# PS2toUSB.net
KiCad netlist of a schematic drawn in EasyEDA Pro
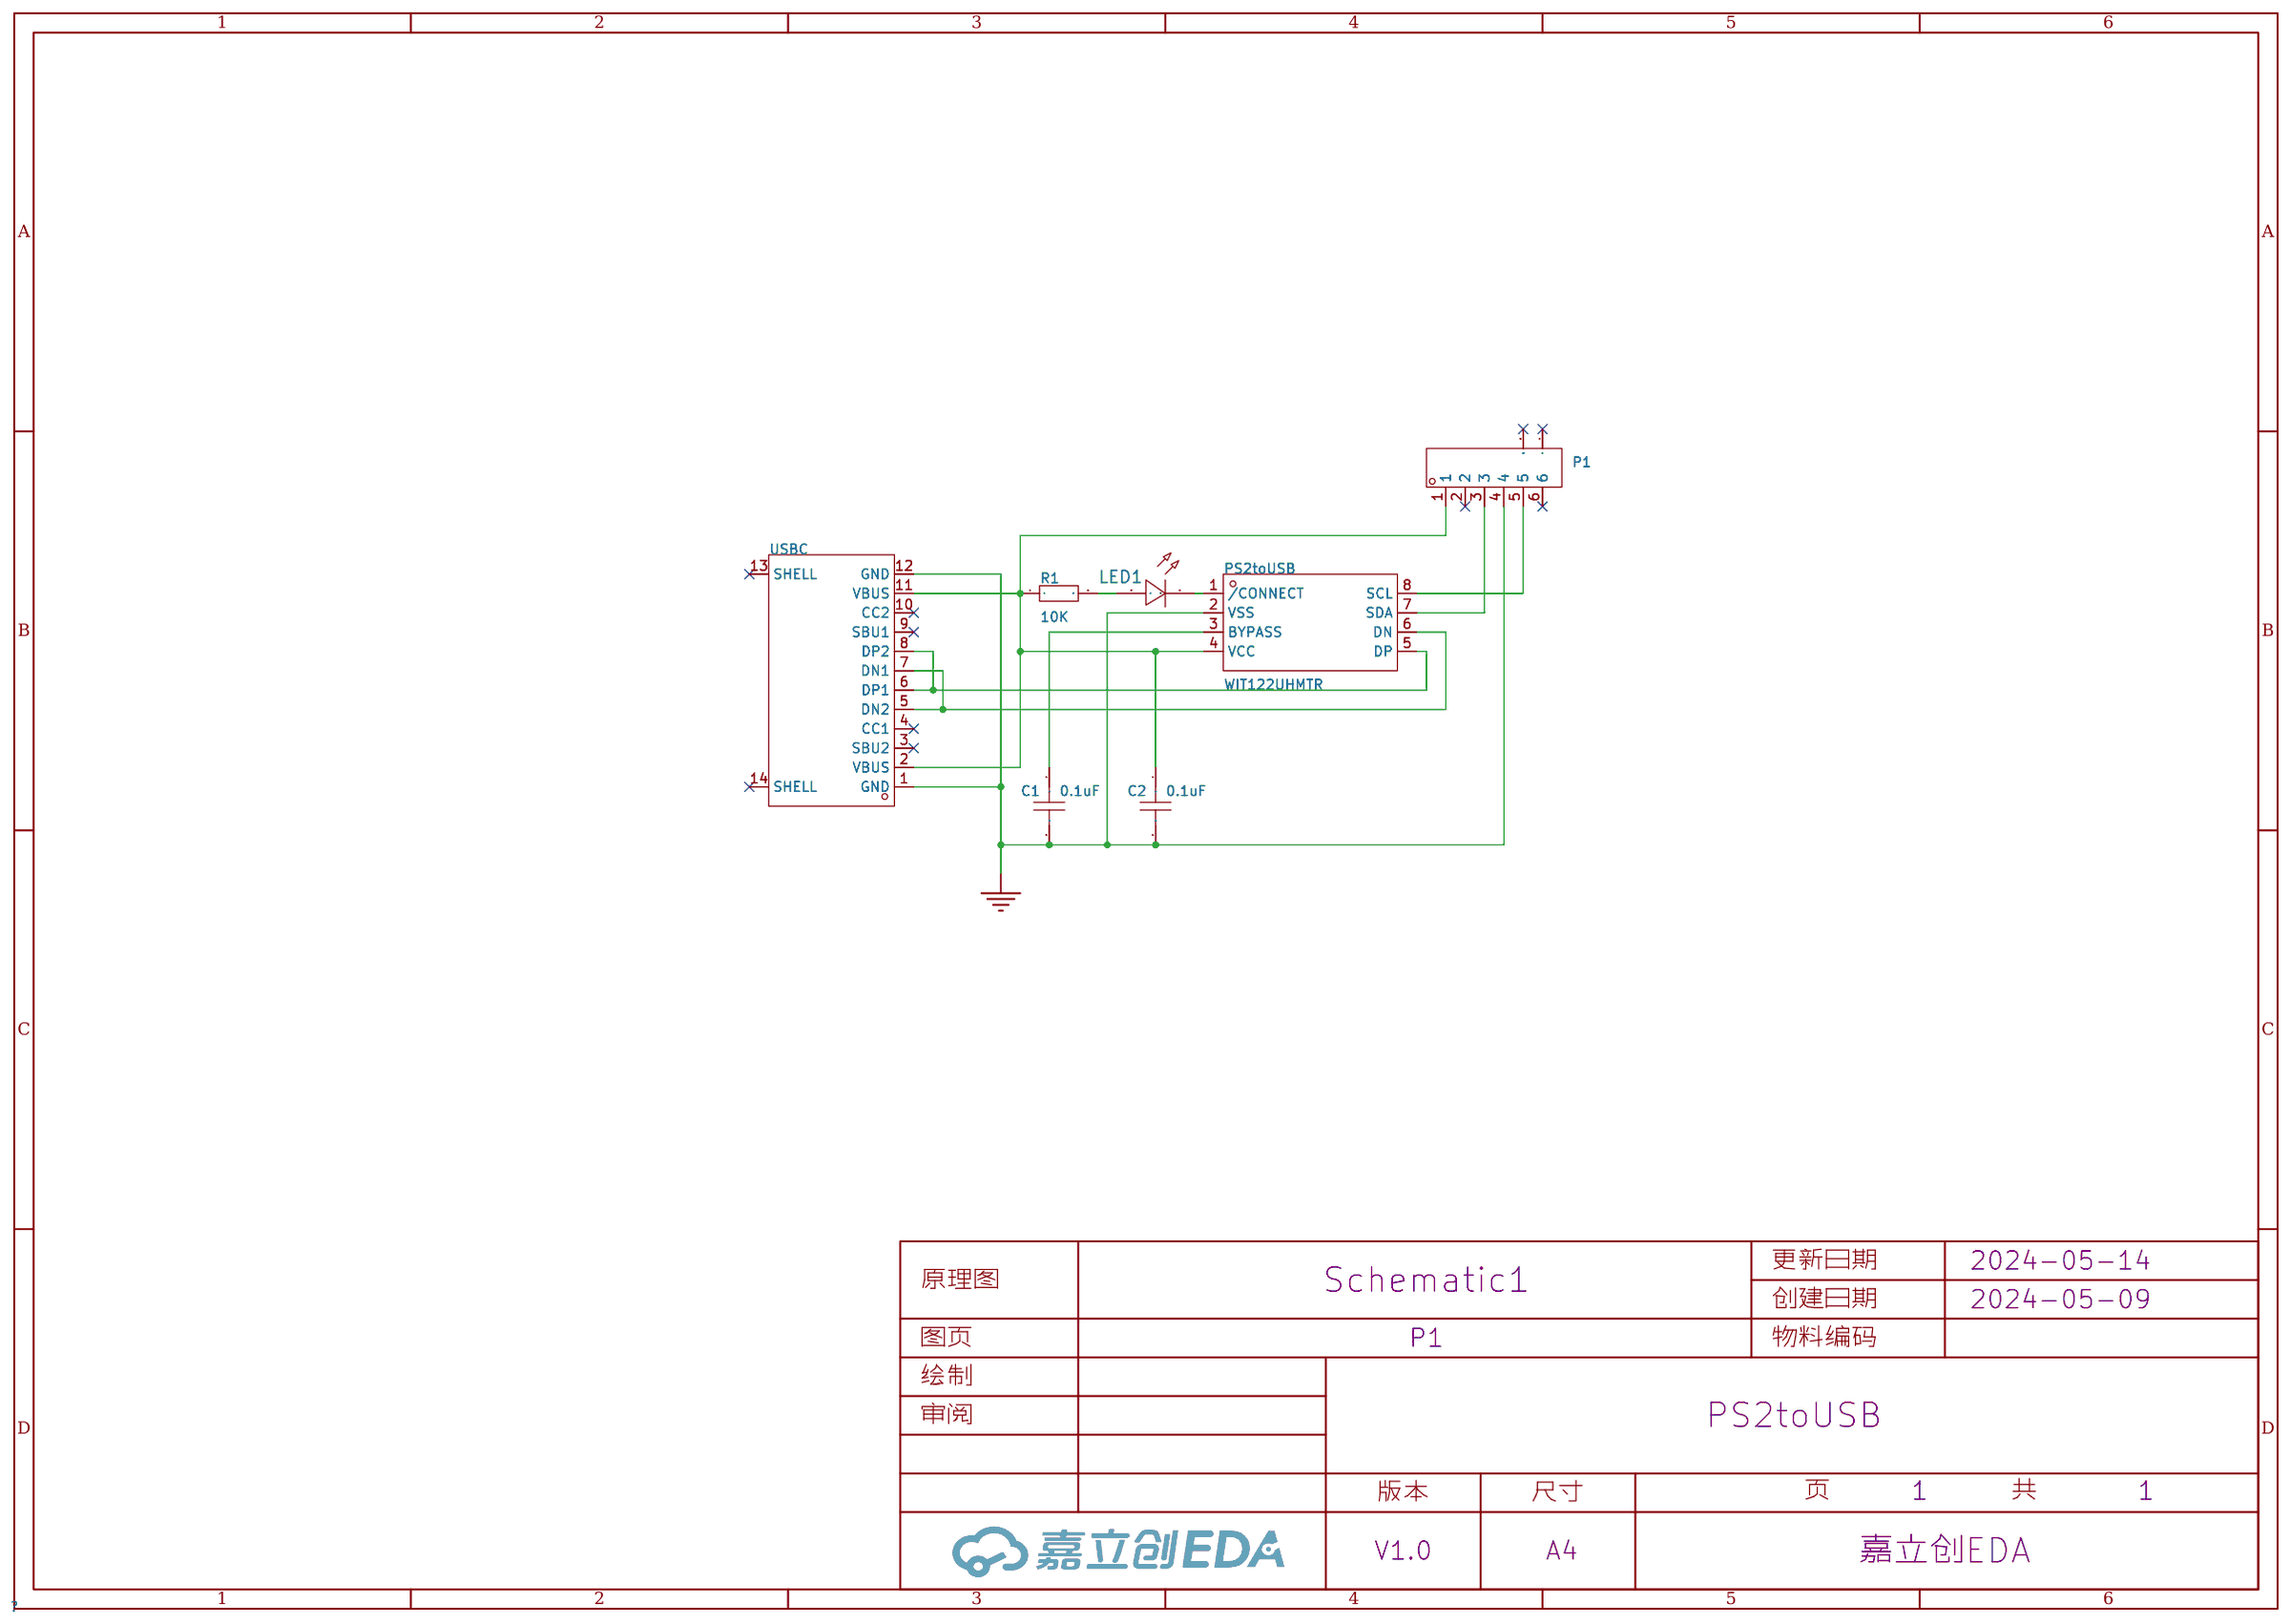
[diagram p0: schematic sheet]

(export (version "E")
  (design (tool "Eeschema 10.0.6"))
  (components
    (comp (ref "C1")
      (value "0.1uF")
      (footprint "easyedapro:C0603")
      (libsource (lib "easyedapro") (part "CapAcitance"))
    )
    (comp (ref "C2")
      (value "0.1uF")
      (footprint "easyedapro:C0603")
      (libsource (lib "easyedapro") (part "CapAcitance"))
    )
    (comp (ref "LED1")
      (value "~")
      (footprint "easyedapro:LED_0603")
      (libsource (lib "easyedapro") (part "LED_R"))
    )
    (comp (ref "P1")
      (value "VCC")
      (footprint "easyedapro:FPC-SMD_C47271")
      (description "锁定特性:抽屉式;触点类型:上接;触点数量:6P;间距:1mm;安装类型:卧贴;工作温度范围:-25°C~+85°C;")
      (fields (field (name "Manufacturer Part") "1.0-6P上接") (field (name "Manufacturer") "BOOMELE(博穆精密)"))
      (libsource (lib "easyedapro") (part "FPC 1.0mmpitch 6P Pull type Pick up"))
    )
    (comp (ref "PS2toUSB")
      (value "WIT122UHMTR")
      (footprint "easyedapro:SOIC-8_L4.9-W3.9-P1.27-LS6.0-TR")
      (libsource (lib "easyedapro") (part "WIT122UHMTR"))
    )
    (comp (ref "R1") (value "10K") (footprint "easyedapro:R0603") (libsource (lib "easyedapro") (part "电阻")))
    (comp (ref "USBC")
      (value "TYPE-C 16PIN 2MD(073)")
      (footprint "easyedapro:USB-C-SMD_TYPE-C-6PIN-2MD-073")
      (description "连接器类型:Type-C;标准:-;公母:母;端口数量:1;触点数量:16P;安装方式:卧贴;额定电流 - 电源:5A;工作温度范围:-25°C~+85°C;")
      (fields (field (name "Manufacturer") "SHOU HAN(首韩)"))
      (libsource (lib "easyedapro") (part "TYPE-C 16PIN 2MD(073)"))
    )
  )
  (nets
    (net (code "1") (name "GND") (class "Default")
      (node (ref "C1") (pin "2") (pinfunction "2_2") (pintype "input"))
      (node (ref "C2") (pin "2") (pinfunction "2_2") (pintype "input"))
      (node (ref "P1") (pin "4") (pinfunction "4_4") (pintype "unspecified"))
      (node (ref "PS2toUSB") (pin "2") (pinfunction "VSS_2") (pintype "unspecified"))
      (node (ref "USBC") (pin "1") (pinfunction "GND_1") (pintype "unspecified"))
      (node (ref "USBC") (pin "12") (pinfunction "GND_12") (pintype "unspecified"))
    )
    (net (code "2") (name "Net-(LED1-A)") (class "Default")
      (node (ref "LED1") (pin "2") (pinfunction "A_2") (pintype "input"))
      (node (ref "R1") (pin "2") (pinfunction "2_2") (pintype "input"))
    )
    (net (code "3") (name "Net-(LED1-C)") (class "Default")
      (node (ref "LED1") (pin "1") (pinfunction "C_1") (pintype "input"))
      (node (ref "PS2toUSB") (pin "1") (pinfunction "/CONNECT_1") (pintype "unspecified"))
    )
    (net (code "4") (name "Net-(PS2toUSB-BYPASS)") (class "Default")
      (node (ref "C1") (pin "1") (pinfunction "1_1") (pintype "input"))
      (node (ref "PS2toUSB") (pin "3") (pinfunction "BYPASS_3") (pintype "unspecified"))
    )
    (net (code "5") (name "Net-(PS2toUSB-DN)") (class "Default")
      (node (ref "PS2toUSB") (pin "6") (pinfunction "DN_6") (pintype "unspecified"))
      (node (ref "USBC") (pin "5") (pinfunction "DN2_5") (pintype "unspecified"))
      (node (ref "USBC") (pin "7") (pinfunction "DN1_7") (pintype "unspecified"))
    )
    (net (code "6") (name "Net-(PS2toUSB-DP)") (class "Default")
      (node (ref "PS2toUSB") (pin "5") (pinfunction "DP_5") (pintype "unspecified"))
      (node (ref "USBC") (pin "6") (pinfunction "DP1_6") (pintype "unspecified"))
      (node (ref "USBC") (pin "8") (pinfunction "DP2_8") (pintype "unspecified"))
    )
    (net (code "7") (name "Net-(PS2toUSB-SCL)") (class "Default")
      (node (ref "P1") (pin "5") (pinfunction "5_5") (pintype "unspecified"))
      (node (ref "PS2toUSB") (pin "8") (pinfunction "SCL_8") (pintype "unspecified"))
    )
    (net (code "8") (name "Net-(PS2toUSB-SDA)") (class "Default")
      (node (ref "P1") (pin "3") (pinfunction "3_3") (pintype "unspecified"))
      (node (ref "PS2toUSB") (pin "7") (pinfunction "SDA_7") (pintype "unspecified"))
    )
    (net (code "9") (name "Net-(PS2toUSB-VCC)") (class "Default")
      (node (ref "C2") (pin "1") (pinfunction "1_1") (pintype "input"))
      (node (ref "P1") (pin "1") (pinfunction "1_1") (pintype "unspecified"))
      (node (ref "PS2toUSB") (pin "4") (pinfunction "VCC_4") (pintype "unspecified"))
      (node (ref "R1") (pin "1") (pinfunction "1_1") (pintype "input"))
      (node (ref "USBC") (pin "11") (pinfunction "VBUS_11") (pintype "unspecified"))
      (node (ref "USBC") (pin "2") (pinfunction "VBUS_2") (pintype "unspecified"))
    )
    (net (code "10") (name "unconnected-(P1-Pad2)") (class "Default")
      (node (ref "P1") (pin "2") (pinfunction "2_2") (pintype "unspecified+no_connect"))
    )
    (net (code "11") (name "unconnected-(P1-Pad6)") (class "Default")
      (node (ref "P1") (pin "6") (pinfunction "6_6") (pintype "unspecified+no_connect"))
    )
    (net (code "12") (name "unconnected-(P1-Pad7)") (class "Default")
      (node (ref "P1") (pin "7") (pinfunction "7_7") (pintype "unspecified+no_connect"))
    )
    (net (code "13") (name "unconnected-(P1-Pad8)") (class "Default")
      (node (ref "P1") (pin "8") (pinfunction "8_8") (pintype "unspecified+no_connect"))
    )
    (net (code "14") (name "unconnected-(USBC-CC1-Pad4)") (class "Default")
      (node (ref "USBC") (pin "4") (pinfunction "CC1_4") (pintype "unspecified+no_connect"))
    )
    (net (code "15") (name "unconnected-(USBC-CC2-Pad10)") (class "Default")
      (node (ref "USBC") (pin "10") (pinfunction "CC2_10") (pintype "unspecified+no_connect"))
    )
    (net (code "16") (name "unconnected-(USBC-SBU1-Pad9)") (class "Default")
      (node (ref "USBC") (pin "9") (pinfunction "SBU1_9") (pintype "unspecified+no_connect"))
    )
    (net (code "17") (name "unconnected-(USBC-SBU2-Pad3)") (class "Default")
      (node (ref "USBC") (pin "3") (pinfunction "SBU2_3") (pintype "unspecified+no_connect"))
    )
    (net (code "18") (name "unconnected-(USBC-SHELL-Pad13)") (class "Default")
      (node (ref "USBC") (pin "13") (pinfunction "SHELL_13") (pintype "unspecified+no_connect"))
    )
    (net (code "19") (name "unconnected-(USBC-SHELL-Pad14)") (class "Default")
      (node (ref "USBC") (pin "14") (pinfunction "SHELL_14") (pintype "unspecified+no_connect"))
    )
  )
)
